# Stoicheia.net
KiCad netlist of a schematic drawn in EAGLE
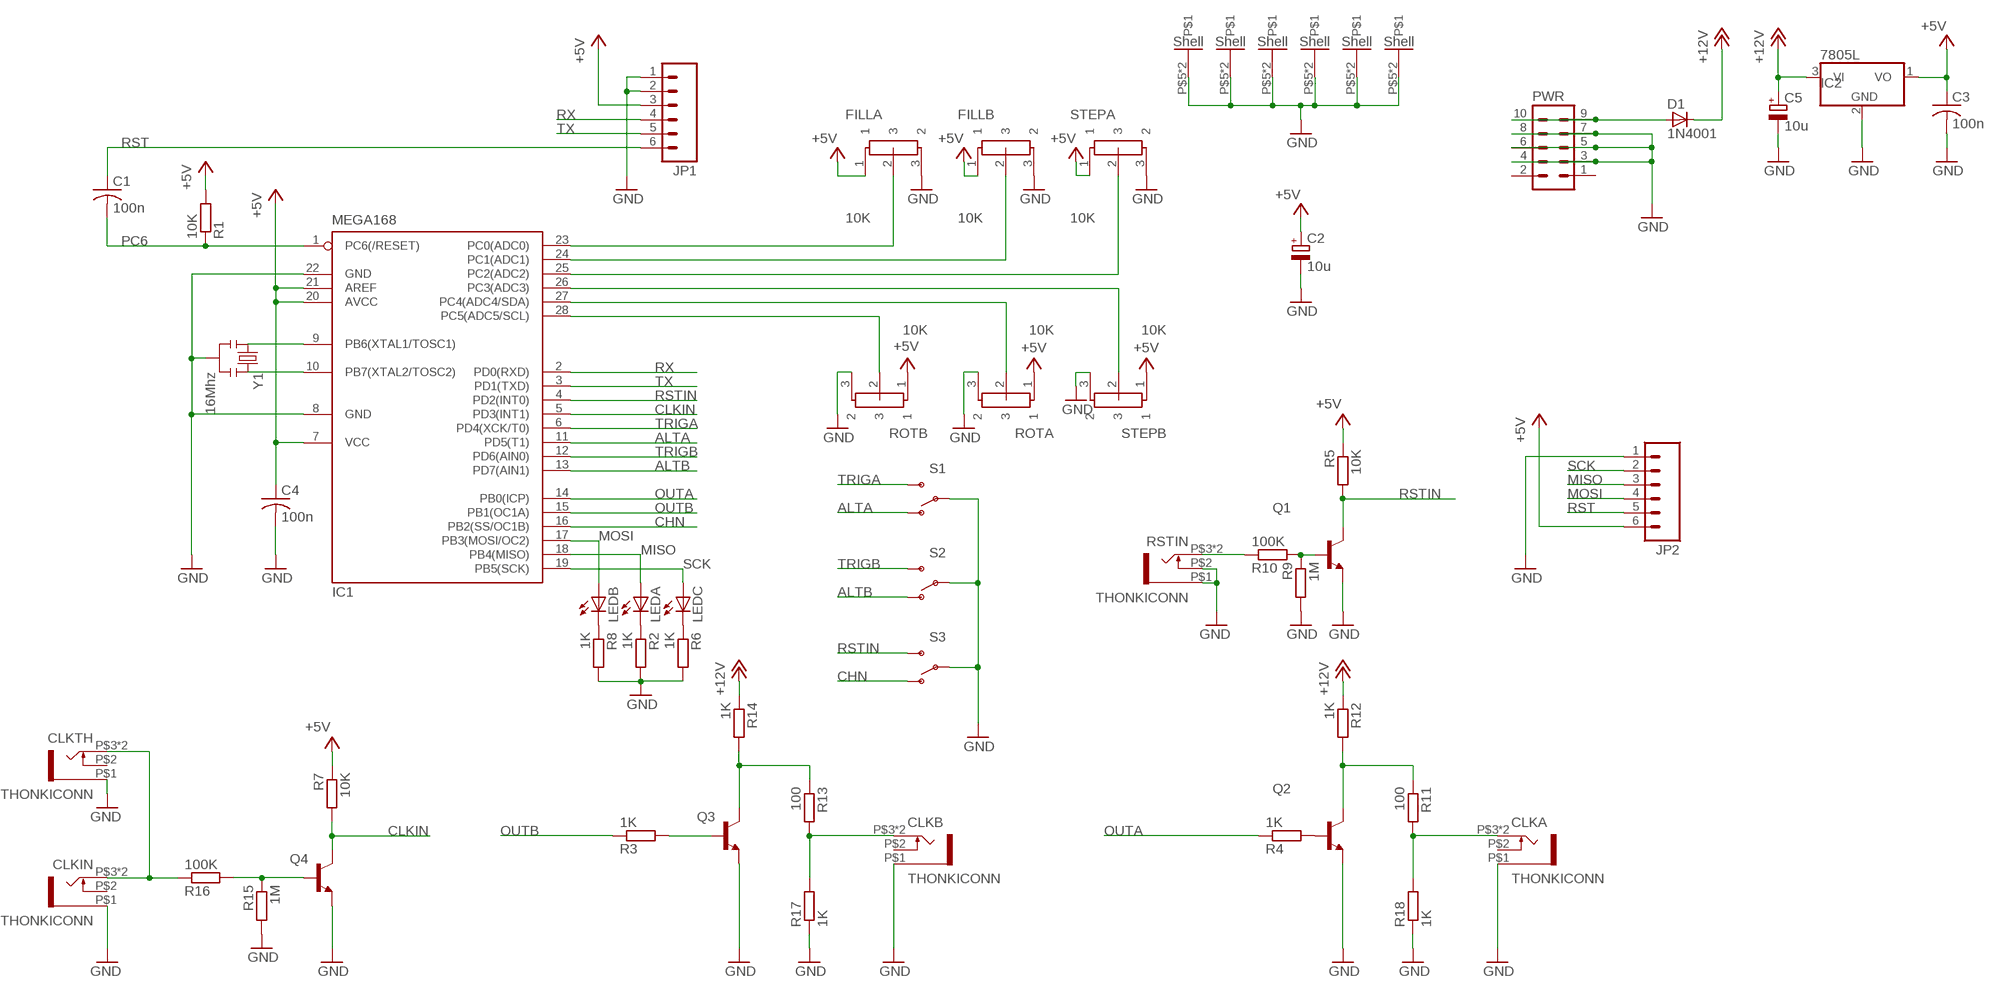
[diagram p0: schematic, sheet 1]

(export (version "E")
  (design (tool "Eeschema 10.0.6"))
  (components
    (comp (ref "C1")
      (value "100n")
      (footprint "eagle-import:C050-024X044")
      (libsource (lib "eagle-import") (part "C-US050-024X044"))
    )
    (comp (ref "C2")
      (value "10u")
      (footprint "eagle-import:E5-6")
      (libsource (lib "eagle-import") (part "CPOL-EUE5-6"))
    )
    (comp (ref "C3")
      (value "100n")
      (footprint "eagle-import:C050-024X044")
      (libsource (lib "eagle-import") (part "C-US050-024X044"))
    )
    (comp (ref "C4")
      (value "100n")
      (footprint "eagle-import:C050-024X044")
      (libsource (lib "eagle-import") (part "C-US050-024X044"))
    )
    (comp (ref "C5")
      (value "10u")
      (footprint "eagle-import:E5-6")
      (libsource (lib "eagle-import") (part "CPOL-EUE5-6"))
    )
    (comp (ref "CLKA")
      (value "THONKICONN")
      (footprint "eagle-import:THONKICONN")
      (libsource (lib "eagle-import") (part "THONKICONN"))
    )
    (comp (ref "CLKB")
      (value "THONKICONN")
      (footprint "eagle-import:THONKICONN")
      (libsource (lib "eagle-import") (part "THONKICONN"))
    )
    (comp (ref "CLKIN")
      (value "THONKICONN")
      (footprint "eagle-import:THONKICONN")
      (libsource (lib "eagle-import") (part "THONKICONN"))
    )
    (comp (ref "CLKTH")
      (value "THONKICONN")
      (footprint "eagle-import:THONKICONN")
      (libsource (lib "eagle-import") (part "THONKICONN"))
    )
    (comp (ref "D1")
      (value "1N4001")
      (footprint "eagle-import:DIODE-1N4001")
      (libsource (lib "eagle-import") (part "DIODE1N4001"))
    )
    (comp (ref "FILLA")
      (value "10K")
      (footprint "eagle-import:POT-ALPS-RK09L1140")
      (libsource (lib "eagle-import") (part "POT-ALPS_ALPS290024"))
    )
    (comp (ref "FILLB")
      (value "10K")
      (footprint "eagle-import:POT-ALPS-RK09L1140")
      (libsource (lib "eagle-import") (part "POT-ALPS_ALPS290024"))
    )
    (comp (ref "IC1")
      (value "MEGA168")
      (footprint "eagle-import:DIL28-3")
      (libsource (lib "eagle-import") (part "MEGA8-P"))
    )
    (comp (ref "IC2")
      (value "7805L")
      (footprint "eagle-import:TO92")
      (libsource (lib "eagle-import") (part "78L05"))
    )
    (comp (ref "JP1")
      (value "M06SIP")
      (footprint "eagle-import:1X06")
      (libsource (lib "eagle-import") (part "M06SIP"))
    )
    (comp (ref "JP2")
      (value "M06SIP")
      (footprint "eagle-import:1X06")
      (libsource (lib "eagle-import") (part "M06SIP"))
    )
    (comp (ref "LEDA")
      (value "LED3MM")
      (footprint "eagle-import:LED3MM")
      (libsource (lib "eagle-import") (part "LED3MM"))
    )
    (comp (ref "LEDB")
      (value "LED3MM")
      (footprint "eagle-import:LED3MM")
      (libsource (lib "eagle-import") (part "LED3MM"))
    )
    (comp (ref "LEDC")
      (value "LED3MM")
      (footprint "eagle-import:LED3MM")
      (libsource (lib "eagle-import") (part "LED3MM"))
    )
    (comp (ref "PWR")
      (value "MA05-2")
      (footprint "eagle-import:MA05-2")
      (libsource (lib "eagle-import") (part "MA05-2"))
    )
    (comp (ref "Q1")
      (value "2N3904-NPN-TO92-EBC")
      (footprint "eagle-import:TO92-EBC")
      (libsource (lib "eagle-import") (part "-NPN-TO92-EBC2N3904"))
    )
    (comp (ref "Q2")
      (value "2N3904-NPN-TO92-EBC")
      (footprint "eagle-import:TO92-EBC")
      (libsource (lib "eagle-import") (part "-NPN-TO92-EBC2N3904"))
    )
    (comp (ref "Q3")
      (value "2N3904-NPN-TO92-EBC")
      (footprint "eagle-import:TO92-EBC")
      (libsource (lib "eagle-import") (part "-NPN-TO92-EBC2N3904"))
    )
    (comp (ref "Q4")
      (value "2N3904-NPN-TO92-EBC")
      (footprint "eagle-import:TO92-EBC")
      (libsource (lib "eagle-import") (part "-NPN-TO92-EBC2N3904"))
    )
    (comp (ref "R1")
      (value "10K")
      (footprint "eagle-import:0204_7")
      (libsource (lib "eagle-import") (part "R-EU_0204/7"))
    )
    (comp (ref "R2")
      (value "1K")
      (footprint "eagle-import:0204_7")
      (libsource (lib "eagle-import") (part "R-EU_0204/7"))
    )
    (comp (ref "R3")
      (value "1K")
      (footprint "eagle-import:0204_7")
      (libsource (lib "eagle-import") (part "R-EU_0204/7"))
    )
    (comp (ref "R4")
      (value "1K")
      (footprint "eagle-import:0204_7")
      (libsource (lib "eagle-import") (part "R-EU_0204/7"))
    )
    (comp (ref "R5")
      (value "10K")
      (footprint "eagle-import:0204_7")
      (libsource (lib "eagle-import") (part "R-EU_0204/7"))
    )
    (comp (ref "R6")
      (value "1K")
      (footprint "eagle-import:0204_7")
      (libsource (lib "eagle-import") (part "R-EU_0204/7"))
    )
    (comp (ref "R7")
      (value "10K")
      (footprint "eagle-import:0204_7")
      (libsource (lib "eagle-import") (part "R-EU_0204/7"))
    )
    (comp (ref "R8")
      (value "1K")
      (footprint "eagle-import:0204_7")
      (libsource (lib "eagle-import") (part "R-EU_0204/7"))
    )
    (comp (ref "R9")
      (value "1M")
      (footprint "eagle-import:0204_7")
      (libsource (lib "eagle-import") (part "R-EU_0204/7"))
    )
    (comp (ref "R10")
      (value "100K")
      (footprint "eagle-import:0204_7")
      (libsource (lib "eagle-import") (part "R-EU_0204/7"))
    )
    (comp (ref "R11")
      (value "100")
      (footprint "eagle-import:0204_7")
      (libsource (lib "eagle-import") (part "R-EU_0204/7"))
    )
    (comp (ref "R12")
      (value "1K")
      (footprint "eagle-import:0204_7")
      (libsource (lib "eagle-import") (part "R-EU_0204/7"))
    )
    (comp (ref "R13")
      (value "100")
      (footprint "eagle-import:0204_7")
      (libsource (lib "eagle-import") (part "R-EU_0204/7"))
    )
    (comp (ref "R14")
      (value "1K")
      (footprint "eagle-import:0204_7")
      (libsource (lib "eagle-import") (part "R-EU_0204/7"))
    )
    (comp (ref "R15")
      (value "1M")
      (footprint "eagle-import:0204_7")
      (libsource (lib "eagle-import") (part "R-EU_0204/7"))
    )
    (comp (ref "R16")
      (value "100K")
      (footprint "eagle-import:0204_7")
      (libsource (lib "eagle-import") (part "R-EU_0204/7"))
    )
    (comp (ref "R17")
      (value "1K")
      (footprint "eagle-import:0204_7")
      (libsource (lib "eagle-import") (part "R-EU_0204/7"))
    )
    (comp (ref "R18")
      (value "1K")
      (footprint "eagle-import:0204_7")
      (libsource (lib "eagle-import") (part "R-EU_0204/7"))
    )
    (comp (ref "ROTA")
      (value "10K")
      (footprint "eagle-import:POT-ALPS-RK09L1140")
      (libsource (lib "eagle-import") (part "POT-ALPS_ALPS290024"))
    )
    (comp (ref "ROTB")
      (value "10K")
      (footprint "eagle-import:POT-ALPS-RK09L1140")
      (libsource (lib "eagle-import") (part "POT-ALPS_ALPS290024"))
    )
    (comp (ref "RSTIN")
      (value "THONKICONN")
      (footprint "eagle-import:THONKICONN")
      (libsource (lib "eagle-import") (part "THONKICONN"))
    )
    (comp (ref "S1")
      (value "SWITCH-SPST")
      (footprint "eagle-import:SWITCH-SPDT-SALECOM-T8014")
      (libsource (lib "eagle-import") (part "SWITCH-SPST"))
    )
    (comp (ref "S2")
      (value "SWITCH-SPST")
      (footprint "eagle-import:SWITCH-SPDT-SALECOM-T8014")
      (libsource (lib "eagle-import") (part "SWITCH-SPST"))
    )
    (comp (ref "S3")
      (value "SWITCH-SPST")
      (footprint "eagle-import:SWITCH-SPDT-SALECOM-T8014")
      (libsource (lib "eagle-import") (part "SWITCH-SPST"))
    )
    (comp (ref "STEPA")
      (value "10K")
      (footprint "eagle-import:POT-ALPS-RK09L1140")
      (libsource (lib "eagle-import") (part "POT-ALPS_ALPS290024"))
    )
    (comp (ref "STEPB")
      (value "10K")
      (footprint "eagle-import:POT-ALPS-RK09L1140")
      (libsource (lib "eagle-import") (part "POT-ALPS_ALPS290024"))
    )
    (comp (ref "Y1")
      (value "16Mhz")
      (footprint "eagle-import:RESONATOR-PTH")
      (libsource (lib "eagle-import") (part "RESONATORPTH"))
    )
  )
  (nets
    (net (code "1") (name "+5V") (class "Default")
      (node (ref "C2") (pin "+") (pinfunction "+_+") (pintype "passive"))
      (node (ref "C3") (pin "1") (pinfunction "1_1") (pintype "passive"))
      (node (ref "C4") (pin "1") (pinfunction "1_1") (pintype "passive"))
      (node (ref "FILLA") (pin "1") (pinfunction "1_1") (pintype "bidirectional"))
      (node (ref "FILLB") (pin "1") (pinfunction "1_1") (pintype "bidirectional"))
      (node (ref "IC1") (pin "20") (pinfunction "AVCC_20") (pintype "power_in"))
      (node (ref "IC1") (pin "21") (pinfunction "AREF_21") (pintype "passive"))
      (node (ref "IC1") (pin "7") (pinfunction "VCC_7") (pintype "power_in"))
      (node (ref "IC2") (pin "1") (pinfunction "VO_1") (pintype "passive"))
      (node (ref "JP1") (pin "3") (pinfunction "3_3") (pintype "passive"))
      (node (ref "JP2") (pin "6") (pinfunction "6_6") (pintype "passive"))
      (node (ref "R1") (pin "2") (pinfunction "2_2") (pintype "passive"))
      (node (ref "R5") (pin "1") (pinfunction "1_1") (pintype "passive"))
      (node (ref "R7") (pin "1") (pinfunction "1_1") (pintype "passive"))
      (node (ref "ROTA") (pin "1") (pinfunction "1_1") (pintype "bidirectional"))
      (node (ref "ROTB") (pin "1") (pinfunction "1_1") (pintype "bidirectional"))
      (node (ref "STEPA") (pin "1") (pinfunction "1_1") (pintype "bidirectional"))
      (node (ref "STEPB") (pin "1") (pinfunction "1_1") (pintype "bidirectional"))
    )
    (net (code "2") (name "+12V") (class "Default")
      (node (ref "C5") (pin "+") (pinfunction "+_+") (pintype "passive"))
      (node (ref "D1") (pin "C") (pinfunction "C_C") (pintype "passive"))
      (node (ref "IC2") (pin "3") (pinfunction "VI_3") (pintype "input"))
      (node (ref "R12") (pin "1") (pinfunction "1_1") (pintype "passive"))
      (node (ref "R14") (pin "1") (pinfunction "1_1") (pintype "passive"))
    )
    (net (code "3") (name "/ALTA") (class "Default")
      (node (ref "IC1") (pin "11") (pinfunction "PD5(T1)_11") (pintype "bidirectional"))
      (node (ref "S1") (pin "1") (pinfunction "O_1") (pintype "passive"))
    )
    (net (code "4") (name "/ALTB") (class "Default")
      (node (ref "IC1") (pin "13") (pinfunction "PD7(AIN1)_13") (pintype "bidirectional"))
      (node (ref "S2") (pin "1") (pinfunction "O_1") (pintype "passive"))
    )
    (net (code "5") (name "/CHN") (class "Default")
      (node (ref "IC1") (pin "16") (pinfunction "PB2(SS/OC1B)_16") (pintype "bidirectional"))
      (node (ref "S3") (pin "1") (pinfunction "O_1") (pintype "passive"))
    )
    (net (code "6") (name "/CLKIN") (class "Default")
      (node (ref "IC1") (pin "5") (pinfunction "PD3(INT1)_5") (pintype "bidirectional"))
      (node (ref "Q4") (pin "C") (pinfunction "C_C") (pintype "passive"))
      (node (ref "R7") (pin "2") (pinfunction "2_2") (pintype "passive"))
    )
    (net (code "7") (name "/MISO") (class "Default")
      (node (ref "IC1") (pin "18") (pinfunction "PB4(MISO)_18") (pintype "bidirectional"))
      (node (ref "JP2") (pin "3") (pinfunction "3_3") (pintype "passive"))
      (node (ref "LEDA") (pin "A") (pinfunction "A_A") (pintype "passive"))
    )
    (net (code "8") (name "/MOSI") (class "Default")
      (node (ref "IC1") (pin "17") (pinfunction "PB3(MOSI/OC2)_17") (pintype "bidirectional"))
      (node (ref "JP2") (pin "4") (pinfunction "4_4") (pintype "passive"))
      (node (ref "LEDB") (pin "A") (pinfunction "A_A") (pintype "passive"))
    )
    (net (code "9") (name "/OUTA") (class "Default")
      (node (ref "IC1") (pin "14") (pinfunction "PB0(ICP)_14") (pintype "bidirectional"))
      (node (ref "R4") (pin "1") (pinfunction "1_1") (pintype "passive"))
    )
    (net (code "10") (name "/OUTB") (class "Default")
      (node (ref "IC1") (pin "15") (pinfunction "PB1(OC1A)_15") (pintype "bidirectional"))
      (node (ref "R3") (pin "1") (pinfunction "1_1") (pintype "passive"))
    )
    (net (code "11") (name "/PC6") (class "Default")
      (node (ref "C1") (pin "2") (pinfunction "2_2") (pintype "passive"))
      (node (ref "IC1") (pin "1") (pinfunction "PC6(/RESET)_1") (pintype "bidirectional"))
      (node (ref "R1") (pin "1") (pinfunction "1_1") (pintype "passive"))
    )
    (net (code "12") (name "/RST") (class "Default")
      (node (ref "C1") (pin "1") (pinfunction "1_1") (pintype "passive"))
      (node (ref "JP1") (pin "6") (pinfunction "6_6") (pintype "passive"))
      (node (ref "JP2") (pin "5") (pinfunction "5_5") (pintype "passive"))
    )
    (net (code "13") (name "/RSTIN") (class "Default")
      (node (ref "IC1") (pin "4") (pinfunction "PD2(INT0)_4") (pintype "bidirectional"))
      (node (ref "Q1") (pin "C") (pinfunction "C_C") (pintype "passive"))
      (node (ref "R5") (pin "2") (pinfunction "2_2") (pintype "passive"))
      (node (ref "S3") (pin "3") (pinfunction "S_3") (pintype "passive"))
    )
    (net (code "14") (name "/RX") (class "Default")
      (node (ref "IC1") (pin "2") (pinfunction "PD0(RXD)_2") (pintype "bidirectional"))
      (node (ref "JP1") (pin "4") (pinfunction "4_4") (pintype "passive"))
    )
    (net (code "15") (name "/SCK") (class "Default")
      (node (ref "IC1") (pin "19") (pinfunction "PB5(SCK)_19") (pintype "bidirectional"))
      (node (ref "JP2") (pin "2") (pinfunction "2_2") (pintype "passive"))
      (node (ref "LEDC") (pin "A") (pinfunction "A_A") (pintype "passive"))
    )
    (net (code "16") (name "/TRIGA") (class "Default")
      (node (ref "IC1") (pin "6") (pinfunction "PD4(XCK/T0)_6") (pintype "bidirectional"))
      (node (ref "S1") (pin "3") (pinfunction "S_3") (pintype "passive"))
    )
    (net (code "17") (name "/TRIGB") (class "Default")
      (node (ref "IC1") (pin "12") (pinfunction "PD6(AIN0)_12") (pintype "bidirectional"))
      (node (ref "S2") (pin "3") (pinfunction "S_3") (pintype "passive"))
    )
    (net (code "18") (name "/TX") (class "Default")
      (node (ref "IC1") (pin "3") (pinfunction "PD1(TXD)_3") (pintype "bidirectional"))
      (node (ref "JP1") (pin "5") (pinfunction "5_5") (pintype "passive"))
    )
    (net (code "19") (name "GND") (class "Default")
      (node (ref "C2") (pin "-") (pinfunction "-_-") (pintype "passive"))
      (node (ref "C3") (pin "2") (pinfunction "2_2") (pintype "passive"))
      (node (ref "C4") (pin "2") (pinfunction "2_2") (pintype "passive"))
      (node (ref "C5") (pin "-") (pinfunction "-_-") (pintype "passive"))
      (node (ref "CLKA") (pin "P$1") (pinfunction "5_P$1") (pintype "passive"))
      (node (ref "CLKB") (pin "P$1") (pinfunction "5_P$1") (pintype "passive"))
      (node (ref "CLKIN") (pin "P$1") (pinfunction "5_P$1") (pintype "passive"))
      (node (ref "CLKTH") (pin "P$1") (pinfunction "5_P$1") (pintype "passive"))
      (node (ref "FILLA") (pin "3") (pinfunction "2_3") (pintype "bidirectional"))
      (node (ref "FILLA") (pin "P$5") (pinfunction "P$1_P$5") (pintype "bidirectional"))
      (node (ref "FILLA") (pin "P$6") (pinfunction "P$1_P$6") (pintype "bidirectional"))
      (node (ref "FILLB") (pin "3") (pinfunction "2_3") (pintype "bidirectional"))
      (node (ref "FILLB") (pin "P$5") (pinfunction "P$1_P$5") (pintype "bidirectional"))
      (node (ref "FILLB") (pin "P$6") (pinfunction "P$1_P$6") (pintype "bidirectional"))
      (node (ref "IC1") (pin "22") (pinfunction "GND_22") (pintype "power_in"))
      (node (ref "IC1") (pin "8") (pinfunction "GND_8") (pintype "power_in"))
      (node (ref "IC2") (pin "2") (pinfunction "GND_2") (pintype "passive"))
      (node (ref "JP1") (pin "1") (pinfunction "1_1") (pintype "passive"))
      (node (ref "JP1") (pin "2") (pinfunction "2_2") (pintype "passive"))
      (node (ref "JP2") (pin "1") (pinfunction "1_1") (pintype "passive"))
      (node (ref "PWR") (pin "3") (pinfunction "3_3") (pintype "passive"))
      (node (ref "PWR") (pin "4") (pinfunction "4_4") (pintype "passive"))
      (node (ref "PWR") (pin "5") (pinfunction "5_5") (pintype "passive"))
      (node (ref "PWR") (pin "6") (pinfunction "6_6") (pintype "passive"))
      (node (ref "PWR") (pin "7") (pinfunction "7_7") (pintype "passive"))
      (node (ref "PWR") (pin "8") (pinfunction "8_8") (pintype "passive"))
      (node (ref "Q1") (pin "E") (pinfunction "E_E") (pintype "passive"))
      (node (ref "Q2") (pin "E") (pinfunction "E_E") (pintype "passive"))
      (node (ref "Q3") (pin "E") (pinfunction "E_E") (pintype "passive"))
      (node (ref "Q4") (pin "E") (pinfunction "E_E") (pintype "passive"))
      (node (ref "R15") (pin "2") (pinfunction "2_2") (pintype "passive"))
      (node (ref "R17") (pin "1") (pinfunction "1_1") (pintype "passive"))
      (node (ref "R18") (pin "1") (pinfunction "1_1") (pintype "passive"))
      (node (ref "R2") (pin "2") (pinfunction "2_2") (pintype "passive"))
      (node (ref "R6") (pin "2") (pinfunction "2_2") (pintype "passive"))
      (node (ref "R8") (pin "2") (pinfunction "2_2") (pintype "passive"))
      (node (ref "R9") (pin "2") (pinfunction "2_2") (pintype "passive"))
      (node (ref "ROTA") (pin "3") (pinfunction "2_3") (pintype "bidirectional"))
      (node (ref "ROTA") (pin "P$5") (pinfunction "P$1_P$5") (pintype "bidirectional"))
      (node (ref "ROTA") (pin "P$6") (pinfunction "P$1_P$6") (pintype "bidirectional"))
      (node (ref "ROTB") (pin "3") (pinfunction "2_3") (pintype "bidirectional"))
      (node (ref "ROTB") (pin "P$5") (pinfunction "P$1_P$5") (pintype "bidirectional"))
      (node (ref "ROTB") (pin "P$6") (pinfunction "P$1_P$6") (pintype "bidirectional"))
      (node (ref "RSTIN") (pin "P$1") (pinfunction "5_P$1") (pintype "passive"))
      (node (ref "RSTIN") (pin "P$2") (pinfunction "4_P$2") (pintype "passive"))
      (node (ref "S1") (pin "2") (pinfunction "P_2") (pintype "passive"))
      (node (ref "S2") (pin "2") (pinfunction "P_2") (pintype "passive"))
      (node (ref "S3") (pin "2") (pinfunction "P_2") (pintype "passive"))
      (node (ref "STEPA") (pin "3") (pinfunction "2_3") (pintype "bidirectional"))
      (node (ref "STEPA") (pin "P$5") (pinfunction "P$1_P$5") (pintype "bidirectional"))
      (node (ref "STEPA") (pin "P$6") (pinfunction "P$1_P$6") (pintype "bidirectional"))
      (node (ref "STEPB") (pin "3") (pinfunction "2_3") (pintype "bidirectional"))
      (node (ref "STEPB") (pin "P$5") (pinfunction "P$1_P$5") (pintype "bidirectional"))
      (node (ref "STEPB") (pin "P$6") (pinfunction "P$1_P$6") (pintype "bidirectional"))
      (node (ref "Y1") (pin "2") (pinfunction "2_2") (pintype "passive"))
    )
    (net (code "20") (name "Net-(CLKA-3-PadP$3)") (class "Default")
      (node (ref "CLKA") (pin "P$3") (pinfunction "3_P$3") (pintype "passive"))
      (node (ref "CLKA") (pin "P$4") (pinfunction "3_P$4") (pintype "passive"))
      (node (ref "R11") (pin "2") (pinfunction "2_2") (pintype "passive"))
      (node (ref "R18") (pin "2") (pinfunction "2_2") (pintype "passive"))
    )
    (net (code "21") (name "Net-(CLKB-3-PadP$3)") (class "Default")
      (node (ref "CLKB") (pin "P$3") (pinfunction "3_P$3") (pintype "passive"))
      (node (ref "CLKB") (pin "P$4") (pinfunction "3_P$4") (pintype "passive"))
      (node (ref "R13") (pin "2") (pinfunction "2_2") (pintype "passive"))
      (node (ref "R17") (pin "2") (pinfunction "2_2") (pintype "passive"))
    )
    (net (code "22") (name "Net-(CLKIN-3-PadP$3)") (class "Default")
      (node (ref "CLKIN") (pin "P$3") (pinfunction "3_P$3") (pintype "passive"))
      (node (ref "CLKIN") (pin "P$4") (pinfunction "3_P$4") (pintype "passive"))
      (node (ref "CLKTH") (pin "P$3") (pinfunction "3_P$3") (pintype "passive"))
      (node (ref "CLKTH") (pin "P$4") (pinfunction "3_P$4") (pintype "passive"))
      (node (ref "R16") (pin "1") (pinfunction "1_1") (pintype "passive"))
    )
    (net (code "23") (name "Net-(D1-PadA)") (class "Default")
      (node (ref "D1") (pin "A") (pinfunction "A_A") (pintype "passive"))
      (node (ref "PWR") (pin "10") (pinfunction "10_10") (pintype "passive"))
      (node (ref "PWR") (pin "9") (pinfunction "9_9") (pintype "passive"))
    )
    (net (code "24") (name "Net-(FILLAA-3)") (class "Default")
      (node (ref "FILLA") (pin "2") (pinfunction "3_2") (pintype "bidirectional"))
      (node (ref "IC1") (pin "23") (pinfunction "PC0(ADC0)_23") (pintype "bidirectional"))
    )
    (net (code "25") (name "Net-(FILLBA-3)") (class "Default")
      (node (ref "FILLB") (pin "2") (pinfunction "3_2") (pintype "bidirectional"))
      (node (ref "IC1") (pin "24") (pinfunction "PC1(ADC1)_24") (pintype "bidirectional"))
    )
    (net (code "26") (name "Net-(IC1-PB6(XTAL1{slash}TOSC1))") (class "Default")
      (node (ref "IC1") (pin "9") (pinfunction "PB6(XTAL1/TOSC1)_9") (pintype "bidirectional"))
      (node (ref "Y1") (pin "1") (pinfunction "1_1") (pintype "passive"))
    )
    (net (code "27") (name "Net-(IC1-PB7(XTAL2{slash}TOSC2))") (class "Default")
      (node (ref "IC1") (pin "10") (pinfunction "PB7(XTAL2/TOSC2)_10") (pintype "bidirectional"))
      (node (ref "Y1") (pin "3") (pinfunction "3_3") (pintype "passive"))
    )
    (net (code "28") (name "Net-(IC1-PC2(ADC2))") (class "Default")
      (node (ref "IC1") (pin "25") (pinfunction "PC2(ADC2)_25") (pintype "bidirectional"))
      (node (ref "STEPA") (pin "2") (pinfunction "3_2") (pintype "bidirectional"))
    )
    (net (code "29") (name "Net-(IC1-PC3(ADC3))") (class "Default")
      (node (ref "IC1") (pin "26") (pinfunction "PC3(ADC3)_26") (pintype "bidirectional"))
      (node (ref "STEPB") (pin "2") (pinfunction "3_2") (pintype "bidirectional"))
    )
    (net (code "30") (name "Net-(IC1-PC4(ADC4{slash}SDA))") (class "Default")
      (node (ref "IC1") (pin "27") (pinfunction "PC4(ADC4/SDA)_27") (pintype "bidirectional"))
      (node (ref "ROTA") (pin "2") (pinfunction "3_2") (pintype "bidirectional"))
    )
    (net (code "31") (name "Net-(IC1-PC5(ADC5{slash}SCL))") (class "Default")
      (node (ref "IC1") (pin "28") (pinfunction "PC5(ADC5/SCL)_28") (pintype "bidirectional"))
      (node (ref "ROTB") (pin "2") (pinfunction "3_2") (pintype "bidirectional"))
    )
    (net (code "32") (name "Net-(LEDA-C)") (class "Default")
      (node (ref "LEDA") (pin "K") (pinfunction "C_K") (pintype "passive"))
      (node (ref "R2") (pin "1") (pinfunction "1_1") (pintype "passive"))
    )
    (net (code "33") (name "Net-(LEDB-C)") (class "Default")
      (node (ref "LEDB") (pin "K") (pinfunction "C_K") (pintype "passive"))
      (node (ref "R8") (pin "1") (pinfunction "1_1") (pintype "passive"))
    )
    (net (code "34") (name "Net-(LEDC-C)") (class "Default")
      (node (ref "LEDC") (pin "K") (pinfunction "C_K") (pintype "passive"))
      (node (ref "R6") (pin "1") (pinfunction "1_1") (pintype "passive"))
    )
    (net (code "35") (name "Net-(Q1-PadB)") (class "Default")
      (node (ref "Q1") (pin "B") (pinfunction "B_B") (pintype "passive"))
      (node (ref "R10") (pin "2") (pinfunction "2_2") (pintype "passive"))
      (node (ref "R9") (pin "1") (pinfunction "1_1") (pintype "passive"))
    )
    (net (code "36") (name "Net-(Q2-PadB)") (class "Default")
      (node (ref "Q2") (pin "B") (pinfunction "B_B") (pintype "passive"))
      (node (ref "R4") (pin "2") (pinfunction "2_2") (pintype "passive"))
    )
    (net (code "37") (name "Net-(Q2-PadC)") (class "Default")
      (node (ref "Q2") (pin "C") (pinfunction "C_C") (pintype "passive"))
      (node (ref "R11") (pin "1") (pinfunction "1_1") (pintype "passive"))
      (node (ref "R12") (pin "2") (pinfunction "2_2") (pintype "passive"))
    )
    (net (code "38") (name "Net-(Q3-PadB)") (class "Default")
      (node (ref "Q3") (pin "B") (pinfunction "B_B") (pintype "passive"))
      (node (ref "R3") (pin "2") (pinfunction "2_2") (pintype "passive"))
    )
    (net (code "39") (name "Net-(Q3-PadC)") (class "Default")
      (node (ref "Q3") (pin "C") (pinfunction "C_C") (pintype "passive"))
      (node (ref "R13") (pin "1") (pinfunction "1_1") (pintype "passive"))
      (node (ref "R14") (pin "2") (pinfunction "2_2") (pintype "passive"))
    )
    (net (code "40") (name "Net-(Q4-PadB)") (class "Default")
      (node (ref "Q4") (pin "B") (pinfunction "B_B") (pintype "passive"))
      (node (ref "R15") (pin "1") (pinfunction "1_1") (pintype "passive"))
      (node (ref "R16") (pin "2") (pinfunction "2_2") (pintype "passive"))
    )
    (net (code "41") (name "Net-(R10-Pad1)") (class "Default")
      (node (ref "R10") (pin "1") (pinfunction "1_1") (pintype "passive"))
      (node (ref "RSTIN") (pin "P$3") (pinfunction "3_P$3") (pintype "passive"))
      (node (ref "RSTIN") (pin "P$4") (pinfunction "3_P$4") (pintype "passive"))
    )
    (net (code "42") (name "unconnected-(CLKA-4-PadP$2)") (class "Default")
      (node (ref "CLKA") (pin "P$2") (pinfunction "4_P$2") (pintype "passive"))
    )
    (net (code "43") (name "unconnected-(CLKB-4-PadP$2)") (class "Default")
      (node (ref "CLKB") (pin "P$2") (pinfunction "4_P$2") (pintype "passive"))
    )
    (net (code "44") (name "unconnected-(CLKIN-4-PadP$2)") (class "Default")
      (node (ref "CLKIN") (pin "P$2") (pinfunction "4_P$2") (pintype "passive"))
    )
    (net (code "45") (name "unconnected-(CLKTH-4-PadP$2)") (class "Default")
      (node (ref "CLKTH") (pin "P$2") (pinfunction "4_P$2") (pintype "passive"))
    )
    (net (code "46") (name "unconnected-(PWR-Pad1)") (class "Default")
      (node (ref "PWR") (pin "1") (pinfunction "1_1") (pintype "passive"))
    )
    (net (code "47") (name "unconnected-(PWR-Pad2)") (class "Default")
      (node (ref "PWR") (pin "2") (pinfunction "2_2") (pintype "passive"))
    )
  )
)
